# SCH_0404_2023-05-09.net
KiCad netlist of a schematic drawn in EasyEDA
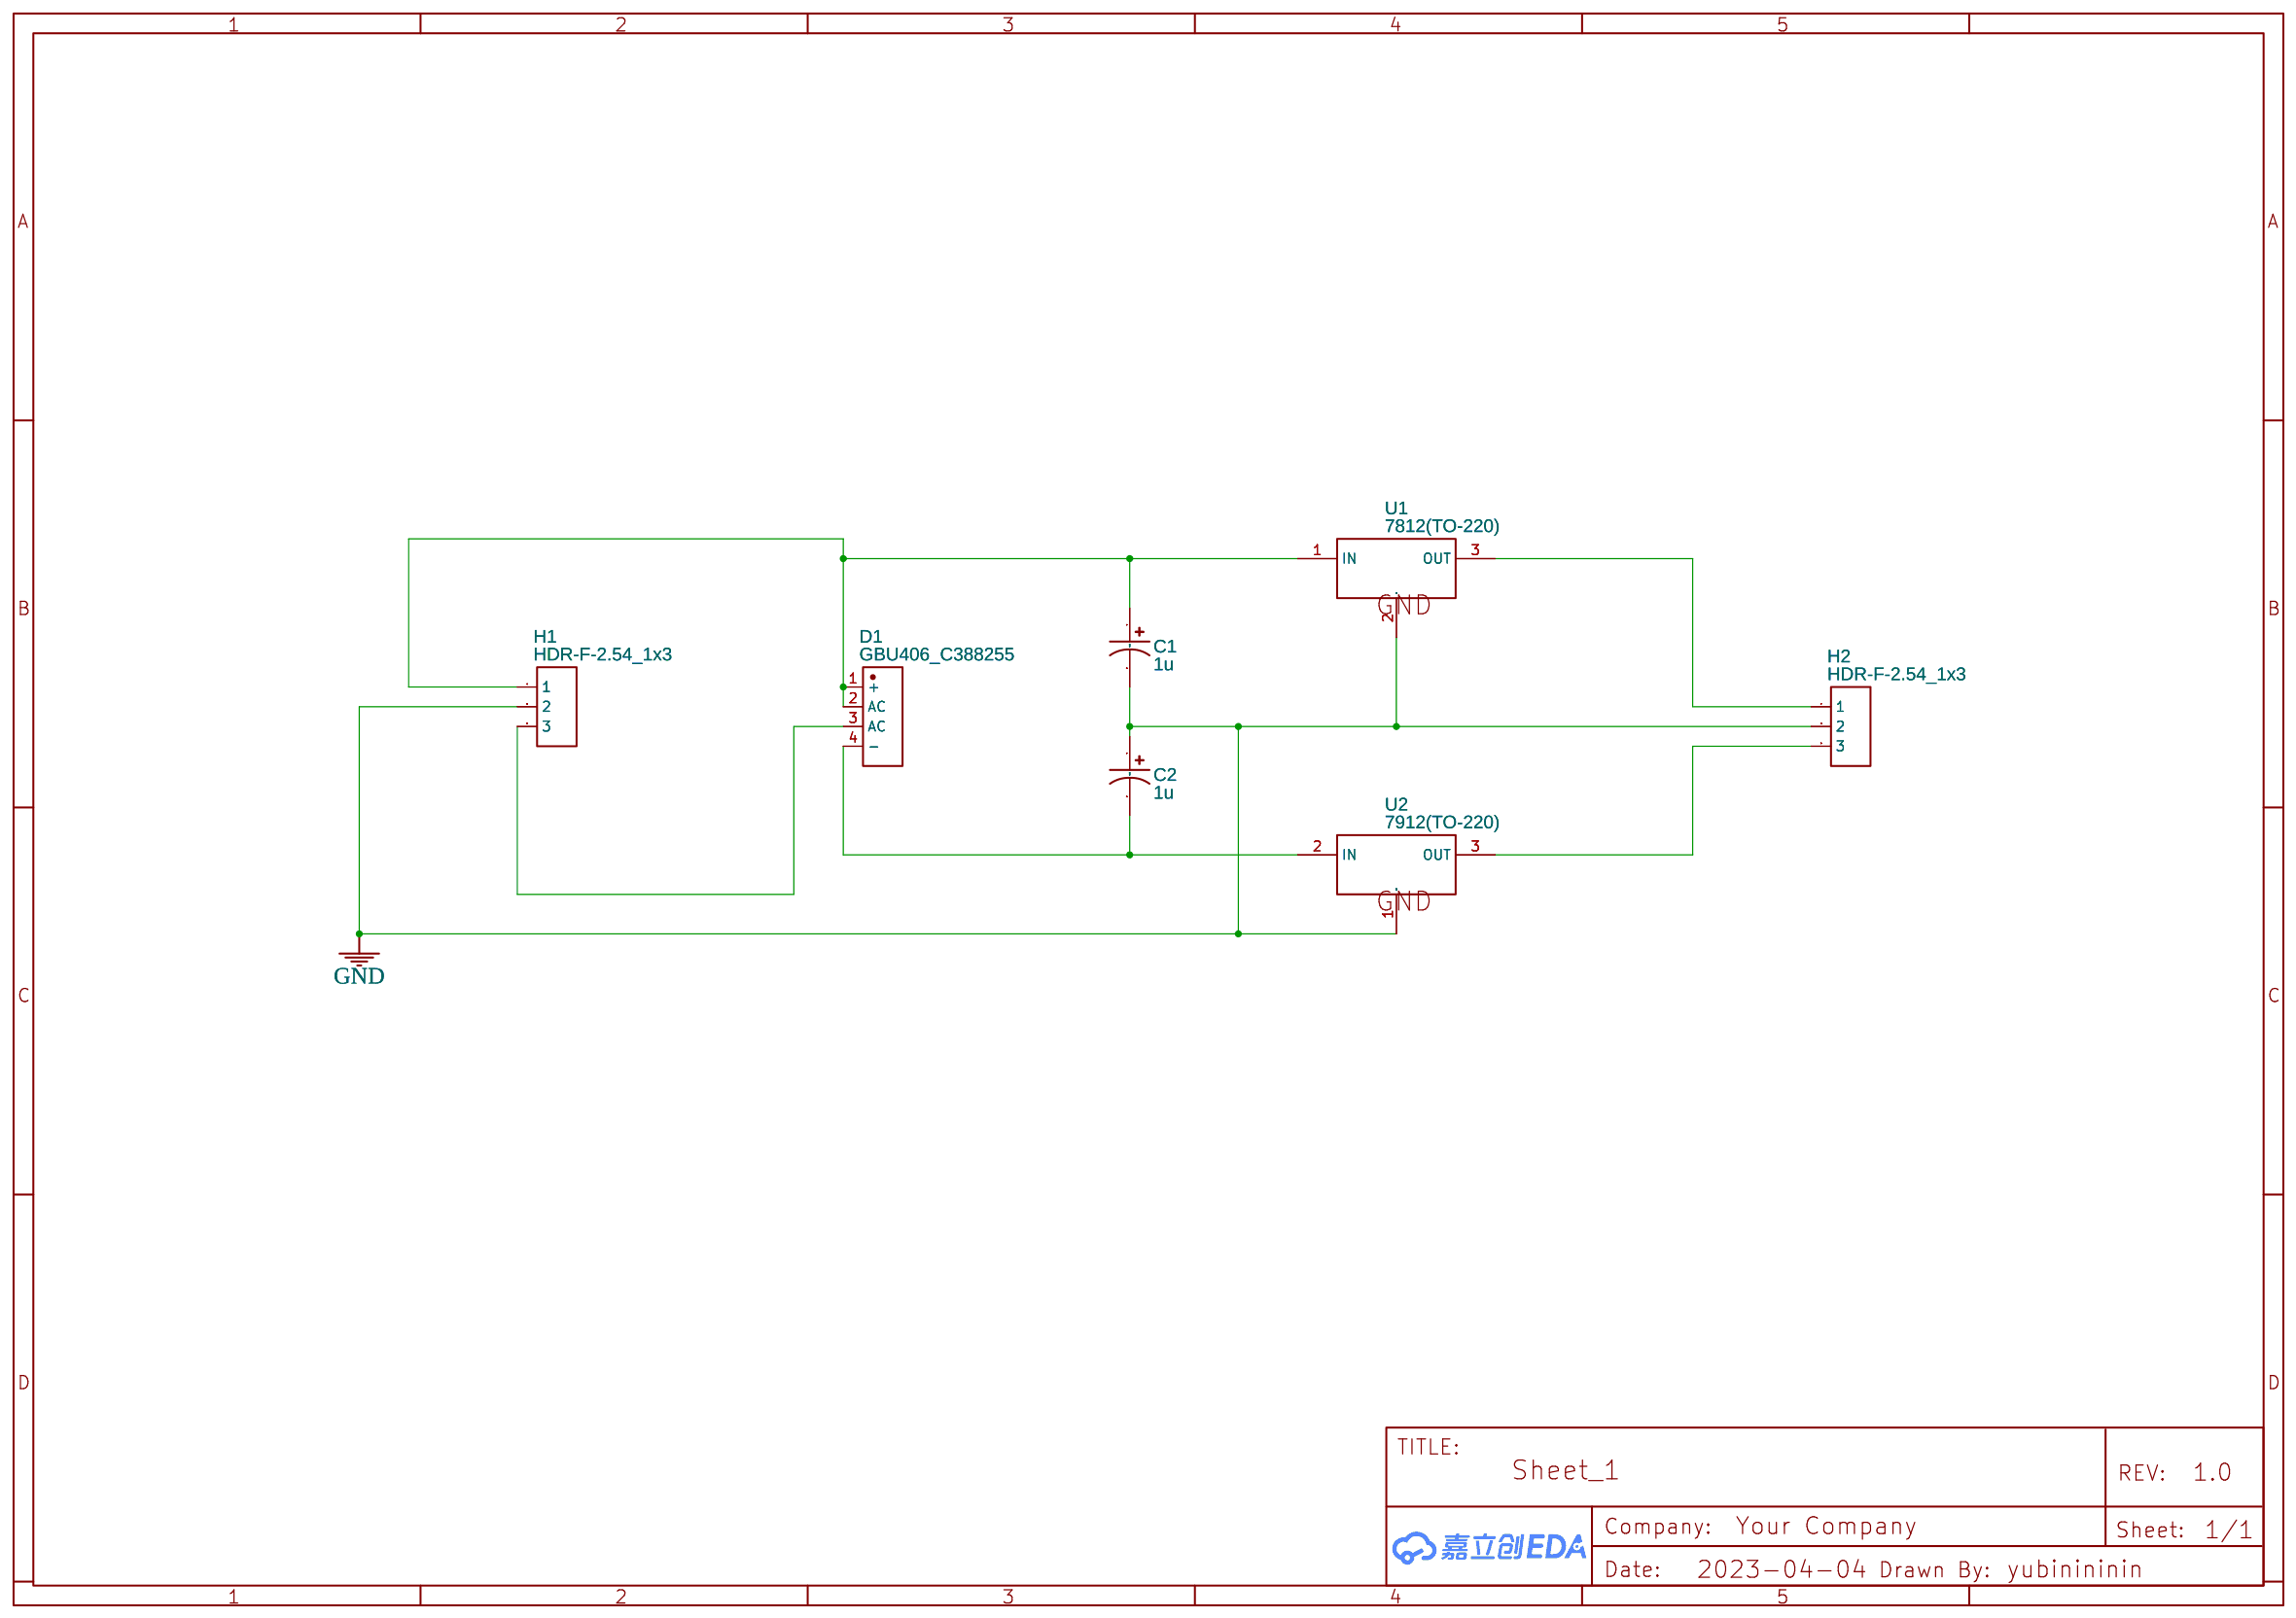
[diagram p0: schematic sheet]

(export (version "E")
  (design (tool "Eeschema 10.0.6"))
  (components
    (comp (ref "C1") (value "1u") (libsource (lib "") (part "C_Tan_SMD_A_US")))
    (comp (ref "C2") (value "1u") (libsource (lib "") (part "C_Tan_SMD_A_US")))
    (comp (ref "D1")
      (value "GBU406_C388255")
      (fields (field (name "BOM_Manufacturer Part") "GBU406") (field (name "BOM_Supplier Part") "C388255"))
      (libsource (lib "") (part "GBU406_C388255"))
    )
    (comp (ref "H1")
      (value "HDR-F-2.54_1x3")
      (fields (field (name "BOM_Supplier Part") "C146690"))
      (libsource (lib "") (part "HDR-F-2.54_1x3"))
    )
    (comp (ref "H2")
      (value "HDR-F-2.54_1x3")
      (fields (field (name "BOM_Supplier Part") "C146690"))
      (libsource (lib "") (part "HDR-F-2.54_1x3"))
    )
    (comp (ref "U1")
      (value "7812(TO-220)")
      (fields (field (name "BOM_Manufacturer Part") "MC7812BTG") (field (name "BOM_Supplier Part") "C45387"))
      (libsource (lib "") (part "7812(TO-220)"))
    )
    (comp (ref "U2")
      (value "7912(TO-220)")
      (fields (field (name "BOM_Manufacturer Part") "L7912CV-DG") (field (name "BOM_Supplier Part") "C3797"))
      (libsource (lib "") (part "7912(TO-220)"))
    )
  )
  (nets
    (net (code "1") (name "GND") (class "Default")
      (node (ref "C1") (pin "2") (pinfunction "2_2") (pintype "unspecified"))
      (node (ref "C2") (pin "1") (pinfunction "1_1") (pintype "unspecified"))
      (node (ref "H1") (pin "2") (pinfunction "2_2") (pintype "input"))
      (node (ref "H2") (pin "2") (pinfunction "2_2") (pintype "input"))
      (node (ref "U1") (pin "2") (pinfunction "GND_2") (pintype "passive"))
      (node (ref "U2") (pin "1") (pinfunction "GND_1") (pintype "passive"))
    )
    (net (code "2") (name "Net-(D1-+)") (class "Default")
      (node (ref "C1") (pin "1") (pinfunction "1_1") (pintype "unspecified"))
      (node (ref "D1") (pin "1") (pinfunction "+_1") (pintype "unspecified"))
      (node (ref "D1") (pin "2") (pinfunction "AC_2") (pintype "unspecified"))
      (node (ref "H1") (pin "1") (pinfunction "1_1") (pintype "input"))
      (node (ref "U1") (pin "1") (pinfunction "IN_1") (pintype "passive"))
    )
    (net (code "3") (name "Net-(D1--)") (class "Default")
      (node (ref "C2") (pin "2") (pinfunction "2_2") (pintype "unspecified"))
      (node (ref "D1") (pin "4") (pinfunction "-_4") (pintype "unspecified"))
      (node (ref "U2") (pin "2") (pinfunction "IN_2") (pintype "passive"))
    )
    (net (code "4") (name "Net-(D1-AC-Pad3)") (class "Default")
      (node (ref "D1") (pin "3") (pinfunction "AC_3") (pintype "unspecified"))
      (node (ref "H1") (pin "3") (pinfunction "3_3") (pintype "input"))
    )
    (net (code "5") (name "Net-(U1-OUT)") (class "Default")
      (node (ref "H2") (pin "1") (pinfunction "1_1") (pintype "input"))
      (node (ref "U1") (pin "3") (pinfunction "OUT_3") (pintype "passive"))
    )
    (net (code "6") (name "Net-(U2-OUT)") (class "Default")
      (node (ref "H2") (pin "3") (pinfunction "3_3") (pintype "input"))
      (node (ref "U2") (pin "3") (pinfunction "OUT_3") (pintype "passive"))
    )
  )
)
